# mLRS-rx-tx-E77-E28-dualband-easysolder-v.net
KiCad netlist of a schematic drawn in EAGLE
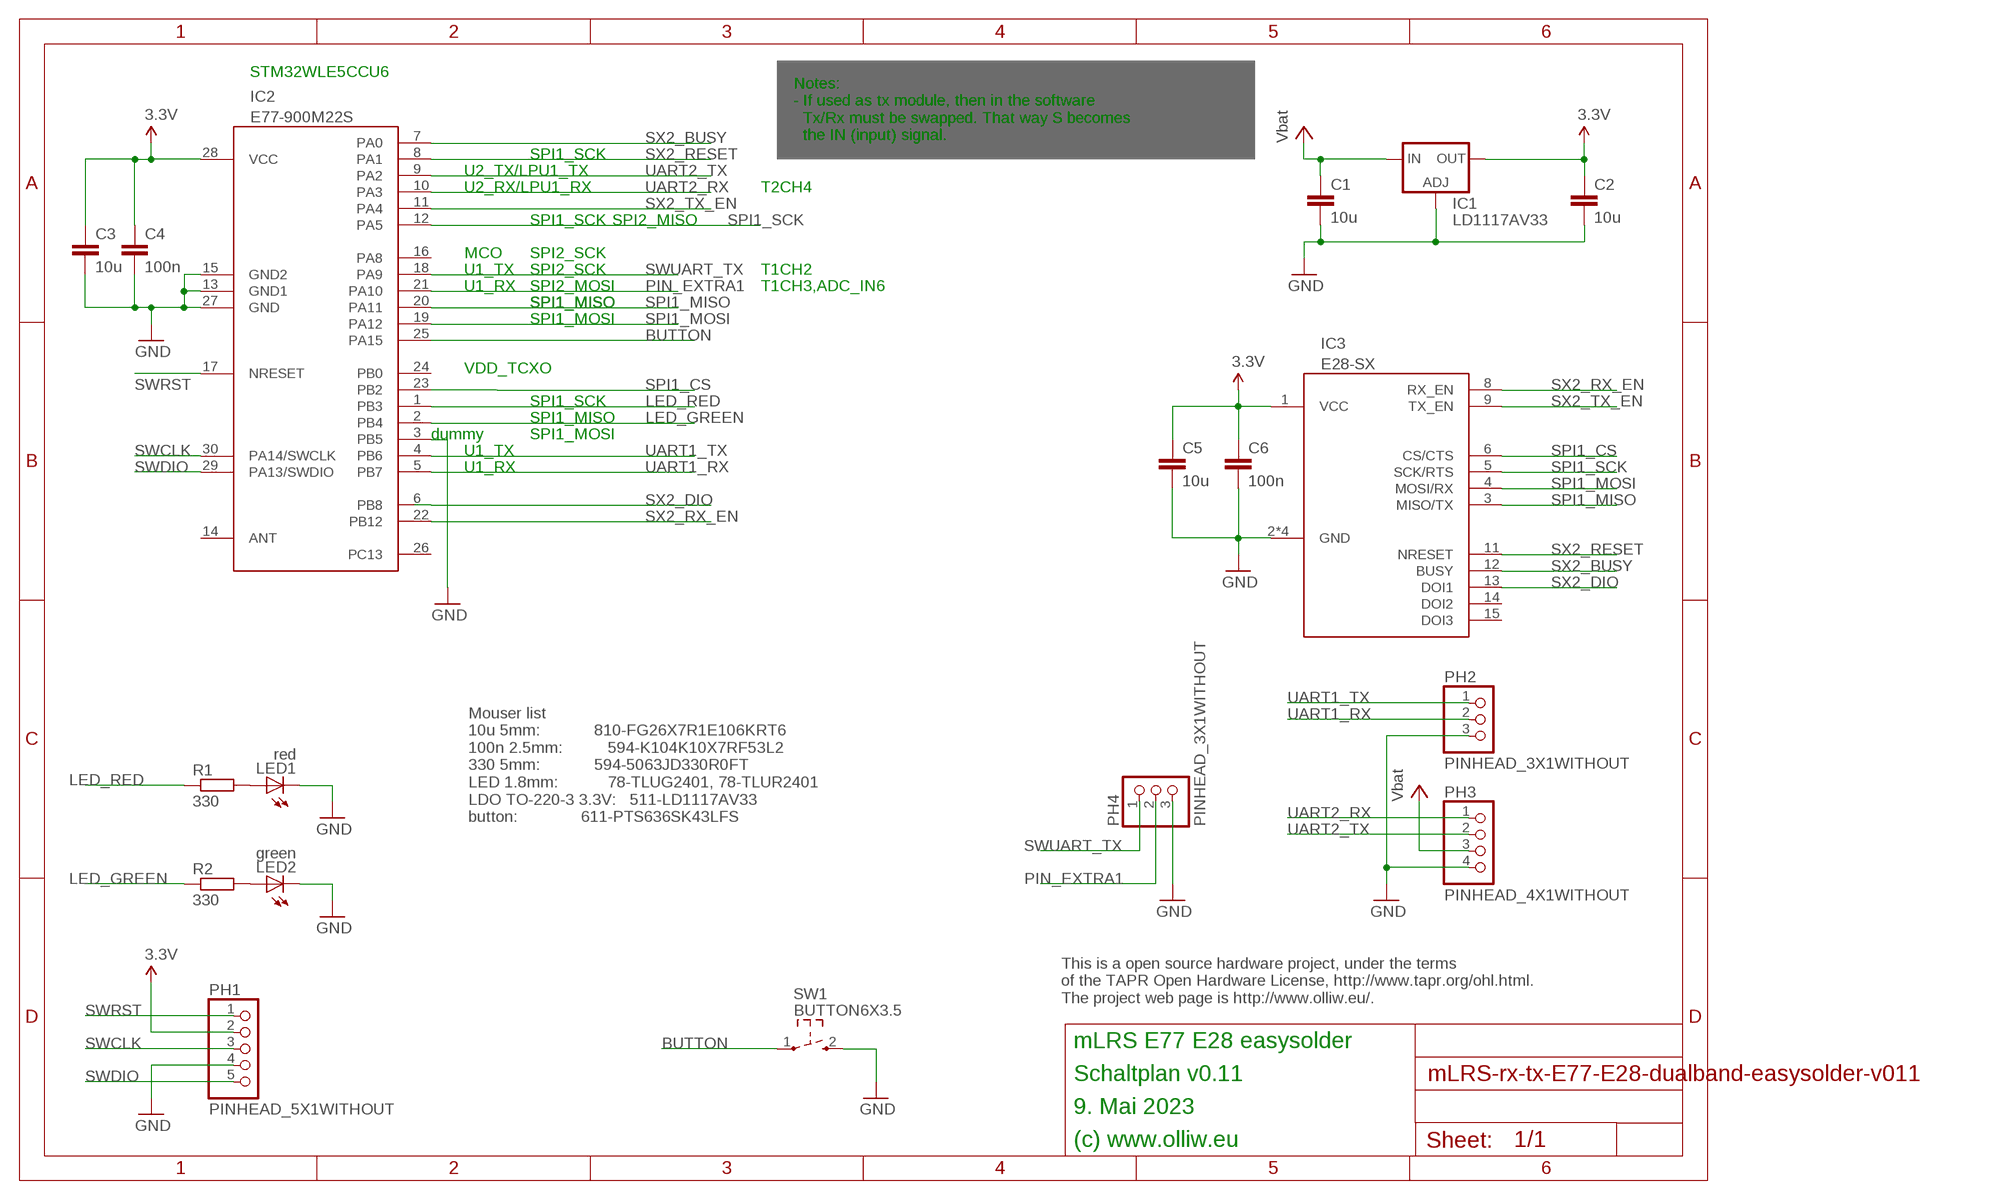
[diagram p0: schematic, sheet 1]

(export (version "E")
  (design (tool "Eeschema 10.0.6"))
  (components
    (comp (ref "C1")
      (value "10u")
      (footprint "eagle-import:C050-045X075")
      (libsource (lib "eagle-import") (part "C-EU050-045X075"))
    )
    (comp (ref "C2")
      (value "10u")
      (footprint "eagle-import:C050-045X075")
      (libsource (lib "eagle-import") (part "C-EU050-045X075"))
    )
    (comp (ref "C3")
      (value "10u")
      (footprint "eagle-import:C050-024X044")
      (libsource (lib "eagle-import") (part "C-EU050-024X044"))
    )
    (comp (ref "C4")
      (value "100n")
      (footprint "eagle-import:C025-024X044")
      (libsource (lib "eagle-import") (part "C-EU025-024X044"))
    )
    (comp (ref "C5")
      (value "10u")
      (footprint "eagle-import:C050-024X044")
      (libsource (lib "eagle-import") (part "C-EU050-024X044"))
    )
    (comp (ref "C6")
      (value "100n")
      (footprint "eagle-import:C025-024X044")
      (libsource (lib "eagle-import") (part "C-EU025-024X044"))
    )
    (comp (ref "IC1")
      (value "LD1117AV33")
      (footprint "eagle-import:TO220L1")
      (libsource (lib "eagle-import") (part "LD117A?V33"))
    )
    (comp (ref "IC2")
      (value "E77-900M22S")
      (footprint "eagle-import:E77-900M22S")
      (libsource (lib "eagle-import") (part "E77-900M22S"))
    )
    (comp (ref "IC3")
      (value "E28-SX")
      (footprint "eagle-import:E28-2G4M27SX")
      (libsource (lib "eagle-import") (part "E28-SX"))
    )
    (comp (ref "LED1")
      (value "red")
      (footprint "eagle-import:LED1.8MM")
      (libsource (lib "eagle-import") (part "LED1.8MM"))
    )
    (comp (ref "LED2")
      (value "green")
      (footprint "eagle-import:LED1.8MM")
      (libsource (lib "eagle-import") (part "LED1.8MM"))
    )
    (comp (ref "PH1")
      (value "PINHEAD_5X1WITHOUT")
      (footprint "eagle-import:PINHEAD_5X1_WO")
      (libsource (lib "eagle-import") (part "PINHEAD_5X1WITHOUT"))
    )
    (comp (ref "PH2")
      (value "PINHEAD_3X1WITHOUT")
      (footprint "eagle-import:PINHEAD_3X1_WO")
      (libsource (lib "eagle-import") (part "PINHEAD_3X1WITHOUT"))
    )
    (comp (ref "PH3")
      (value "PINHEAD_4X1WITHOUT")
      (footprint "eagle-import:PINHEAD_4X1_WO")
      (libsource (lib "eagle-import") (part "PINHEAD_4X1WITHOUT"))
    )
    (comp (ref "PH4")
      (value "PINHEAD_3X1WITHOUT")
      (footprint "eagle-import:PINHEAD_3X1_WO")
      (libsource (lib "eagle-import") (part "PINHEAD_3X1WITHOUT"))
    )
    (comp (ref "R1")
      (value "330")
      (footprint "eagle-import:R0204_6.25")
      (libsource (lib "eagle-import") (part "R_EUR0204/6.25"))
    )
    (comp (ref "R2")
      (value "330")
      (footprint "eagle-import:R0204_6.25")
      (libsource (lib "eagle-import") (part "R_EUR0204/6.25"))
    )
    (comp (ref "SW1")
      (value "BUTTON6X3.5")
      (footprint "eagle-import:BUTTON-THT")
      (libsource (lib "eagle-import") (part "BUTTON6X3.5"))
    )
  )
  (nets
    (net (code "1") (name "/BUTTON") (class "Default")
      (node (ref "IC2") (pin "25") (pinfunction "PA15_25") (pintype "bidirectional"))
      (node (ref "SW1") (pin "1") (pinfunction "1_1") (pintype "passive"))
    )
    (net (code "2") (name "/LED_GREEN") (class "Default")
      (node (ref "IC2") (pin "2") (pinfunction "PB4_2") (pintype "bidirectional"))
      (node (ref "R2") (pin "1") (pinfunction "1_1") (pintype "passive"))
    )
    (net (code "3") (name "/LED_RED") (class "Default")
      (node (ref "IC2") (pin "1") (pinfunction "PB3_1") (pintype "bidirectional"))
      (node (ref "R1") (pin "1") (pinfunction "1_1") (pintype "passive"))
    )
    (net (code "4") (name "/PIN_EXTRA1") (class "Default")
      (node (ref "IC2") (pin "21") (pinfunction "PA10_21") (pintype "bidirectional"))
      (node (ref "PH4") (pin "2") (pinfunction "3_2") (pintype "passive"))
    )
    (net (code "5") (name "/SPI1_CS") (class "Default")
      (node (ref "IC2") (pin "23") (pinfunction "PB2_23") (pintype "bidirectional"))
      (node (ref "IC3") (pin "6") (pinfunction "CS/CTS_6") (pintype "bidirectional"))
    )
    (net (code "6") (name "/SPI1_MISO") (class "Default")
      (node (ref "IC2") (pin "20") (pinfunction "PA11_20") (pintype "bidirectional"))
      (node (ref "IC3") (pin "3") (pinfunction "MISO/TX_3") (pintype "bidirectional"))
    )
    (net (code "7") (name "/SPI1_MOSI") (class "Default")
      (node (ref "IC2") (pin "19") (pinfunction "PA12_19") (pintype "bidirectional"))
      (node (ref "IC3") (pin "4") (pinfunction "MOSI/RX_4") (pintype "bidirectional"))
    )
    (net (code "8") (name "/SPI1_SCK") (class "Default")
      (node (ref "IC2") (pin "12") (pinfunction "PA5_12") (pintype "bidirectional"))
      (node (ref "IC3") (pin "5") (pinfunction "SCK/RTS_5") (pintype "bidirectional"))
    )
    (net (code "9") (name "/SWCLK") (class "Default")
      (node (ref "IC2") (pin "30") (pinfunction "PA14/SWCLK_30") (pintype "bidirectional"))
      (node (ref "PH1") (pin "3") (pinfunction "3_3") (pintype "passive"))
    )
    (net (code "10") (name "/SWDIO") (class "Default")
      (node (ref "IC2") (pin "29") (pinfunction "PA13/SWDIO_29") (pintype "bidirectional"))
      (node (ref "PH1") (pin "5") (pinfunction "5_5") (pintype "passive"))
    )
    (net (code "11") (name "/SWRST") (class "Default")
      (node (ref "IC2") (pin "17") (pinfunction "NRESET_17") (pintype "input"))
      (node (ref "PH1") (pin "1") (pinfunction "1_1") (pintype "passive"))
    )
    (net (code "12") (name "/SWUART_TX") (class "Default")
      (node (ref "IC2") (pin "18") (pinfunction "PA9_18") (pintype "bidirectional"))
      (node (ref "PH4") (pin "1") (pinfunction "1_1") (pintype "passive"))
    )
    (net (code "13") (name "/SX2_BUSY") (class "Default")
      (node (ref "IC2") (pin "7") (pinfunction "PA0_7") (pintype "bidirectional"))
      (node (ref "IC3") (pin "12") (pinfunction "BUSY_12") (pintype "bidirectional"))
    )
    (net (code "14") (name "/SX2_DIO") (class "Default")
      (node (ref "IC2") (pin "6") (pinfunction "PB8_6") (pintype "bidirectional"))
      (node (ref "IC3") (pin "13") (pinfunction "DOI1_13") (pintype "bidirectional"))
    )
    (net (code "15") (name "/SX2_RESET") (class "Default")
      (node (ref "IC2") (pin "8") (pinfunction "PA1_8") (pintype "bidirectional"))
      (node (ref "IC3") (pin "11") (pinfunction "NRESET_11") (pintype "input"))
    )
    (net (code "16") (name "/SX2_RX_EN") (class "Default")
      (node (ref "IC2") (pin "22") (pinfunction "PB12_22") (pintype "bidirectional"))
      (node (ref "IC3") (pin "8") (pinfunction "RX_EN_8") (pintype "bidirectional"))
    )
    (net (code "17") (name "/SX2_TX_EN") (class "Default")
      (node (ref "IC2") (pin "11") (pinfunction "PA4_11") (pintype "bidirectional"))
      (node (ref "IC3") (pin "9") (pinfunction "TX_EN_9") (pintype "bidirectional"))
    )
    (net (code "18") (name "/UART1_RX") (class "Default")
      (node (ref "IC2") (pin "5") (pinfunction "PB7_5") (pintype "bidirectional"))
      (node (ref "PH2") (pin "2") (pinfunction "3_2") (pintype "passive"))
    )
    (net (code "19") (name "/UART1_TX") (class "Default")
      (node (ref "IC2") (pin "4") (pinfunction "PB6_4") (pintype "bidirectional"))
      (node (ref "PH2") (pin "1") (pinfunction "1_1") (pintype "passive"))
    )
    (net (code "20") (name "/UART2_RX") (class "Default")
      (node (ref "IC2") (pin "10") (pinfunction "PA3_10") (pintype "bidirectional"))
      (node (ref "PH3") (pin "1") (pinfunction "1_1") (pintype "passive"))
    )
    (net (code "21") (name "/UART2_TX") (class "Default")
      (node (ref "IC2") (pin "9") (pinfunction "PA2_9") (pintype "bidirectional"))
      (node (ref "PH3") (pin "2") (pinfunction "2_2") (pintype "passive"))
    )
    (net (code "22") (name "3.3V") (class "Default")
      (node (ref "C2") (pin "1") (pinfunction "1_1") (pintype "passive"))
      (node (ref "C3") (pin "1") (pinfunction "1_1") (pintype "passive"))
      (node (ref "C4") (pin "1") (pinfunction "1_1") (pintype "passive"))
      (node (ref "C5") (pin "1") (pinfunction "1_1") (pintype "passive"))
      (node (ref "C6") (pin "1") (pinfunction "1_1") (pintype "passive"))
      (node (ref "IC1") (pin "2") (pinfunction "OUT_2") (pintype "passive"))
      (node (ref "IC2") (pin "28") (pinfunction "VCC_28") (pintype "power_in"))
      (node (ref "IC3") (pin "1") (pinfunction "VCC_1") (pintype "power_in"))
      (node (ref "PH1") (pin "2") (pinfunction "2_2") (pintype "passive"))
    )
    (net (code "23") (name "GND") (class "Default")
      (node (ref "C1") (pin "2") (pinfunction "2_2") (pintype "passive"))
      (node (ref "C2") (pin "2") (pinfunction "2_2") (pintype "passive"))
      (node (ref "C3") (pin "2") (pinfunction "2_2") (pintype "passive"))
      (node (ref "C4") (pin "2") (pinfunction "2_2") (pintype "passive"))
      (node (ref "C5") (pin "2") (pinfunction "2_2") (pintype "passive"))
      (node (ref "C6") (pin "2") (pinfunction "2_2") (pintype "passive"))
      (node (ref "IC1") (pin "1") (pinfunction "ADJ_1") (pintype "input"))
      (node (ref "IC2") (pin "13") (pinfunction "GND1_13") (pintype "power_in"))
      (node (ref "IC2") (pin "15") (pinfunction "GND2_15") (pintype "power_in"))
      (node (ref "IC2") (pin "27") (pinfunction "GND_27") (pintype "power_in"))
      (node (ref "IC2") (pin "3") (pinfunction "PB5_3") (pintype "bidirectional"))
      (node (ref "IC3") (pin "10") (pinfunction "GND_10") (pintype "power_in"))
      (node (ref "IC3") (pin "16") (pinfunction "GND_16") (pintype "power_in"))
      (node (ref "IC3") (pin "2") (pinfunction "GND_2") (pintype "power_in"))
      (node (ref "IC3") (pin "7") (pinfunction "GND_7") (pintype "power_in"))
      (node (ref "LED1") (pin "K") (pinfunction "C_K") (pintype "passive"))
      (node (ref "LED2") (pin "K") (pinfunction "C_K") (pintype "passive"))
      (node (ref "PH1") (pin "4") (pinfunction "4_4") (pintype "passive"))
      (node (ref "PH2") (pin "3") (pinfunction "5_3") (pintype "passive"))
      (node (ref "PH3") (pin "4") (pinfunction "4_4") (pintype "passive"))
      (node (ref "PH4") (pin "3") (pinfunction "5_3") (pintype "passive"))
      (node (ref "SW1") (pin "2") (pinfunction "3_2") (pintype "passive"))
    )
    (net (code "24") (name "Net-(LED1-PadA)") (class "Default")
      (node (ref "LED1") (pin "A") (pinfunction "A_A") (pintype "passive"))
      (node (ref "R1") (pin "2") (pinfunction "2_2") (pintype "passive"))
    )
    (net (code "25") (name "Net-(LED2-PadA)") (class "Default")
      (node (ref "LED2") (pin "A") (pinfunction "A_A") (pintype "passive"))
      (node (ref "R2") (pin "2") (pinfunction "2_2") (pintype "passive"))
    )
    (net (code "26") (name "Vbat") (class "Default")
      (node (ref "C1") (pin "1") (pinfunction "1_1") (pintype "passive"))
      (node (ref "IC1") (pin "3") (pinfunction "IN_3") (pintype "input"))
      (node (ref "PH3") (pin "3") (pinfunction "3_3") (pintype "passive"))
    )
    (net (code "27") (name "unconnected-(IC2-ANT-Pad14)") (class "Default")
      (node (ref "IC2") (pin "14") (pinfunction "ANT_14") (pintype "bidirectional"))
    )
    (net (code "28") (name "unconnected-(IC2-PA8-Pad16)") (class "Default")
      (node (ref "IC2") (pin "16") (pinfunction "PA8_16") (pintype "bidirectional"))
    )
    (net (code "29") (name "unconnected-(IC2-PB0-Pad24)") (class "Default")
      (node (ref "IC2") (pin "24") (pinfunction "PB0_24") (pintype "bidirectional"))
    )
    (net (code "30") (name "unconnected-(IC2-PC13-Pad26)") (class "Default")
      (node (ref "IC2") (pin "26") (pinfunction "PC13_26") (pintype "bidirectional"))
    )
    (net (code "31") (name "unconnected-(IC3-DOI2-Pad14)") (class "Default")
      (node (ref "IC3") (pin "14") (pinfunction "DOI2_14") (pintype "bidirectional"))
    )
    (net (code "32") (name "unconnected-(IC3-DOI3-Pad15)") (class "Default")
      (node (ref "IC3") (pin "15") (pinfunction "DOI3_15") (pintype "bidirectional"))
    )
  )
)
